# parts_servo.net
KiCad netlist of a schematic drawn in EAGLE
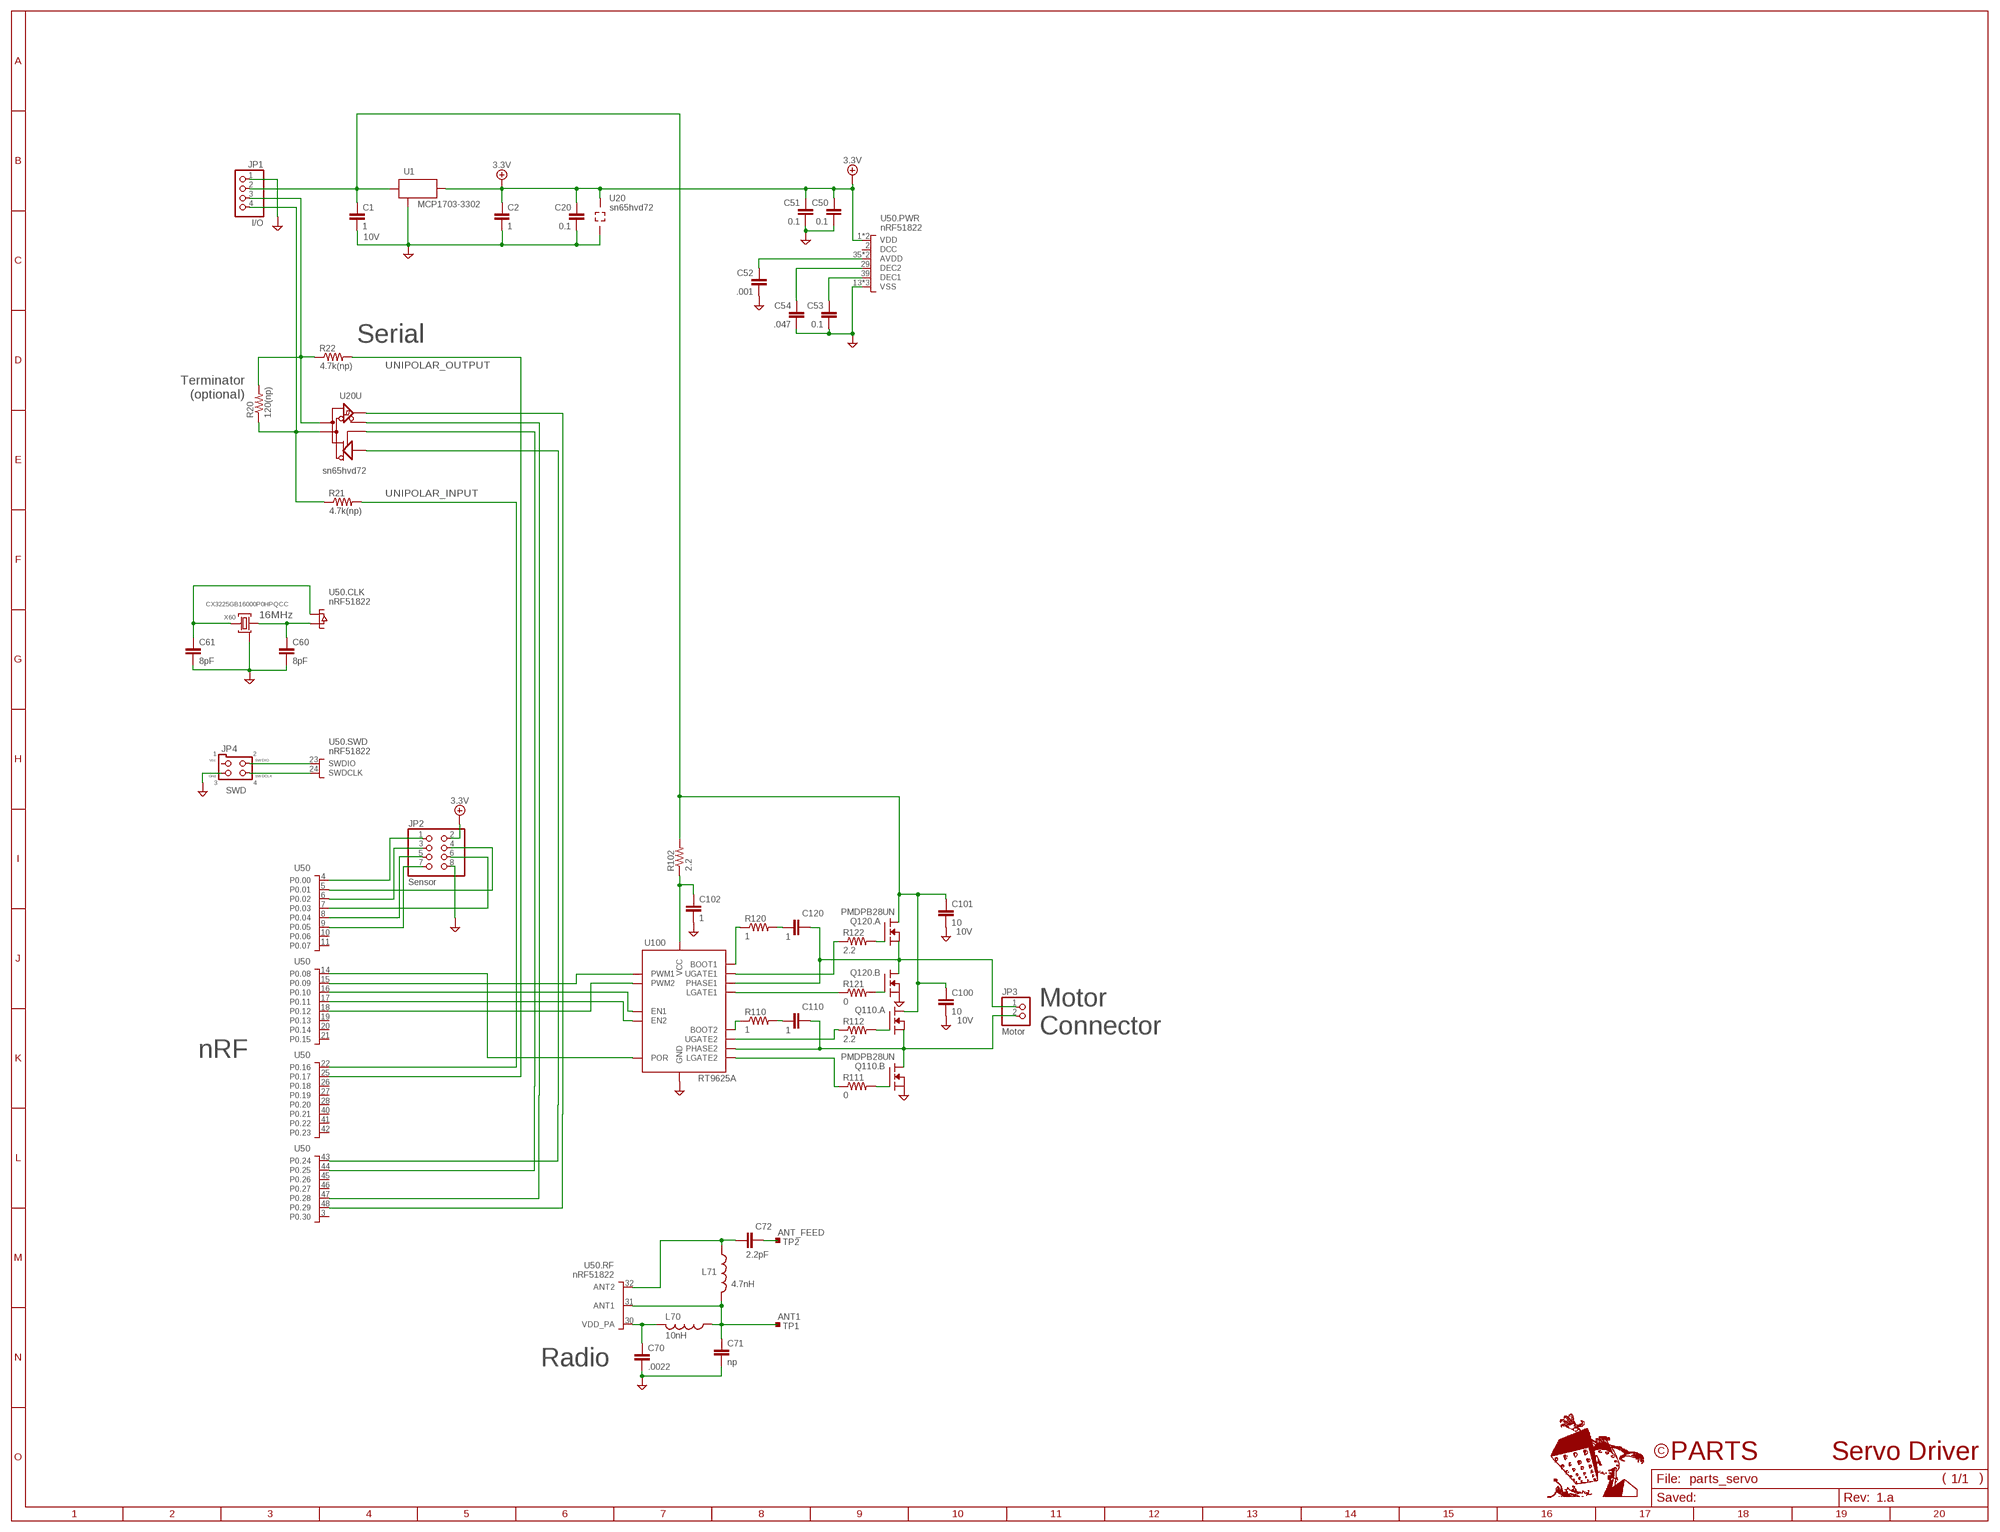
[diagram p0: schematic, sheet 1]

(export (version "E")
  (design (tool "Eeschema 10.0.6"))
  (components
    (comp (ref "C1")
      (value "1")
      (footprint "eagle-import:0402-B")
      (fields (field (name "VOLTAGE") "10V"))
      (libsource (lib "eagle-import") (part "C-EU0402-B"))
    )
    (comp (ref "C2")
      (value "1")
      (footprint "eagle-import:0402-B")
      (libsource (lib "eagle-import") (part "C-EU0402-B"))
    )
    (comp (ref "C20")
      (value "0.1")
      (footprint "eagle-import:0402-B")
      (libsource (lib "eagle-import") (part "C-EU0402-B"))
    )
    (comp (ref "C50")
      (value "0.1")
      (footprint "eagle-import:0402-B")
      (libsource (lib "eagle-import") (part "C-EU0402-B"))
    )
    (comp (ref "C51")
      (value "0.1")
      (footprint "eagle-import:0402-B")
      (libsource (lib "eagle-import") (part "C-EU0402-B"))
    )
    (comp (ref "C52")
      (value ".001")
      (footprint "eagle-import:0402-B")
      (libsource (lib "eagle-import") (part "C-EU0402-B"))
    )
    (comp (ref "C53")
      (value "0.1")
      (footprint "eagle-import:0402-B")
      (libsource (lib "eagle-import") (part "C-EU0402-B"))
    )
    (comp (ref "C54")
      (value ".047")
      (footprint "eagle-import:0402-B")
      (libsource (lib "eagle-import") (part "C-EU0402-B"))
    )
    (comp (ref "C60")
      (value "8pF")
      (footprint "eagle-import:0402-B")
      (libsource (lib "eagle-import") (part "C-EU0402-B"))
    )
    (comp (ref "C61")
      (value "8pF")
      (footprint "eagle-import:0402-B")
      (libsource (lib "eagle-import") (part "C-EU0402-B"))
    )
    (comp (ref "C70")
      (value ".0022")
      (footprint "eagle-import:0402-B")
      (libsource (lib "eagle-import") (part "C-EU0402-B"))
    )
    (comp (ref "C71")
      (value "np")
      (footprint "eagle-import:0402-B")
      (libsource (lib "eagle-import") (part "C-EU0402-B"))
    )
    (comp (ref "C72")
      (value "2.2pF")
      (footprint "eagle-import:0402-B")
      (libsource (lib "eagle-import") (part "C-EU0402-B"))
    )
    (comp (ref "C100")
      (value "10")
      (footprint "eagle-import:0805-B")
      (fields (field (name "VOLTAGE") "10V"))
      (libsource (lib "eagle-import") (part "C-EU0805-B"))
    )
    (comp (ref "C101")
      (value "10")
      (footprint "eagle-import:0805-B")
      (fields (field (name "VOLTAGE") "10V"))
      (libsource (lib "eagle-import") (part "C-EU0805-B"))
    )
    (comp (ref "C102")
      (value "1")
      (footprint "eagle-import:0402-B")
      (libsource (lib "eagle-import") (part "C-EU0402-B"))
    )
    (comp (ref "C110")
      (value "1")
      (footprint "eagle-import:0402-B")
      (libsource (lib "eagle-import") (part "C-EU0402-B"))
    )
    (comp (ref "C120")
      (value "1")
      (footprint "eagle-import:0402-B")
      (libsource (lib "eagle-import") (part "C-EU0402-B"))
    )
    (comp (ref "JP1")
      (value "I/O")
      (footprint "eagle-import:1X04")
      (libsource (lib "eagle-import") (part "PINHD-1X4"))
    )
    (comp (ref "JP2")
      (value "Sensor")
      (footprint "eagle-import:2X04")
      (libsource (lib "eagle-import") (part "PINHD-2X4"))
    )
    (comp (ref "JP3")
      (value "Motor")
      (footprint "eagle-import:1X02")
      (libsource (lib "eagle-import") (part "PINHD-1X2"))
    )
    (comp (ref "JP4")
      (value "SWD")
      (footprint "eagle-import:PINHEADER-2X2-0.05_IN")
      (libsource (lib "eagle-import") (part "SWD-ARM_MINI"))
    )
    (comp (ref "L70")
      (value "10nH")
      (footprint "eagle-import:0402-B")
      (libsource (lib "eagle-import") (part "L-US0402-B"))
    )
    (comp (ref "L71")
      (value "4.7nH")
      (footprint "eagle-import:0402-B")
      (libsource (lib "eagle-import") (part "L-US0402-B"))
    )
    (comp (ref "Q110")
      (value "PMDPB28UN")
      (footprint "eagle-import:DFN-6(2X2)+2EP(TRANSISTOR)")
      (libsource (lib "eagle-import") (part "NFET-DUAL-DFN-6(2X2)+2PADS"))
    )
    (comp (ref "Q120")
      (value "PMDPB28UN")
      (footprint "eagle-import:DFN-6(2X2)+2EP(TRANSISTOR)")
      (libsource (lib "eagle-import") (part "NFET-DUAL-DFN-6(2X2)+2PADS"))
    )
    (comp (ref "R20")
      (value "120(np)")
      (footprint "eagle-import:0402-B")
      (libsource (lib "eagle-import") (part "R-US_0402-B"))
    )
    (comp (ref "R21")
      (value "4.7k(np)")
      (footprint "eagle-import:0402-B")
      (libsource (lib "eagle-import") (part "R-US_0402-B"))
    )
    (comp (ref "R22")
      (value "4.7k(np)")
      (footprint "eagle-import:0402-B")
      (libsource (lib "eagle-import") (part "R-US_0402-B"))
    )
    (comp (ref "R102")
      (value "2.2")
      (footprint "eagle-import:0402-B")
      (libsource (lib "eagle-import") (part "R-US_0402-B"))
    )
    (comp (ref "R110")
      (value "1")
      (footprint "eagle-import:0402-B")
      (libsource (lib "eagle-import") (part "R-US_0402-B"))
    )
    (comp (ref "R111")
      (value "0")
      (footprint "eagle-import:0402-B")
      (libsource (lib "eagle-import") (part "R-US_0402-B"))
    )
    (comp (ref "R112")
      (value "2.2")
      (footprint "eagle-import:0402-B")
      (libsource (lib "eagle-import") (part "R-US_0402-B"))
    )
    (comp (ref "R120")
      (value "1")
      (footprint "eagle-import:0402-B")
      (libsource (lib "eagle-import") (part "R-US_0402-B"))
    )
    (comp (ref "R121")
      (value "0")
      (footprint "eagle-import:0402-B")
      (libsource (lib "eagle-import") (part "R-US_0402-B"))
    )
    (comp (ref "R122")
      (value "2.2")
      (footprint "eagle-import:0402-B")
      (libsource (lib "eagle-import") (part "R-US_0402-B"))
    )
    (comp (ref "TP1")
      (value "ANT1")
      (footprint "eagle-import:TESTPOINT-(1X1)CREAMED")
      (libsource (lib "eagle-import") (part "TESTPAD-(1X1)CREAMED"))
    )
    (comp (ref "TP2")
      (value "ANT_FEED")
      (footprint "eagle-import:TESTPOINT-(1X1)CREAMED")
      (libsource (lib "eagle-import") (part "TESTPAD-(1X1)CREAMED"))
    )
    (comp (ref "U1")
      (value "MCP1703-3302")
      (footprint "eagle-import:DFN-8(2X3)+EP")
      (libsource (lib "eagle-import") (part "VOLTAGE_REGULATOR-3_TERMINAL"))
    )
    (comp (ref "U20")
      (value "sn65hvd72")
      (footprint "eagle-import:DFN-8(3X3)+EP")
      (libsource (lib "eagle-import") (part "DIFFERENTIAL_TRANSCEIVER-DFN-8(3X3)+EP"))
    )
    (comp (ref "U50")
      (value "nRF51822")
      (footprint "eagle-import:DFN-48(6X6)+EP")
      (fields (field (name "SWDIO") "(nRST)"))
      (libsource (lib "eagle-import") (part "NRF51822-QFN-48(6X6)"))
    )
    (comp (ref "U100")
      (value "RT9625A")
      (footprint "eagle-import:QFN-16(4X4)+EP")
      (libsource (lib "eagle-import") (part "HALF_BRIDGE_DRIVER-DUAL-QFN-16(4X4)"))
    )
    (comp (ref "X60")
      (value "CX3225GB16000P0HPQCC")
      (footprint "eagle-import:CRYSTAL-3.2X2.5(4_TERMINAL)")
      (fields (field (name "FREQUENCY") "16MHz"))
      (libsource (lib "eagle-import") (part "CRYSTAL_SHIELDED-3.2X2.5"))
    )
  )
  (nets
    (net (code "1") (name "/UNIPOLAR_INPUT") (class "Default")
      (node (ref "R21") (pin "2") (pinfunction "2_2") (pintype "passive"))
      (node (ref "U50") (pin "22") (pinfunction "P0.16_22") (pintype "bidirectional"))
    )
    (net (code "2") (name "/UNIPOLAR_OUTPUT") (class "Default")
      (node (ref "R22") (pin "2") (pinfunction "2_2") (pintype "passive"))
      (node (ref "U50") (pin "25") (pinfunction "P0.17_25") (pintype "bidirectional"))
    )
    (net (code "3") (name "3.3V") (class "Default")
      (node (ref "C2") (pin "1") (pinfunction "1_1") (pintype "passive"))
      (node (ref "C20") (pin "1") (pinfunction "1_1") (pintype "passive"))
      (node (ref "C50") (pin "1") (pinfunction "1_1") (pintype "passive"))
      (node (ref "C51") (pin "1") (pinfunction "1_1") (pintype "passive"))
      (node (ref "JP2") (pin "2") (pinfunction "2_2") (pintype "passive"))
      (node (ref "U1") (pin "1") (pinfunction "OUT_1") (pintype "power_in"))
      (node (ref "U20") (pin "8") (pinfunction "VDD_8") (pintype "power_in"))
      (node (ref "U50") (pin "1") (pinfunction "VDD_1") (pintype "power_in"))
      (node (ref "U50") (pin "12") (pinfunction "VDD_12") (pintype "power_in"))
    )
    (net (code "4") (name "GND_TRIANGLE-GND") (class "Default")
      (node (ref "C1") (pin "2") (pinfunction "2_2") (pintype "passive"))
      (node (ref "C100") (pin "2") (pinfunction "2_2") (pintype "passive"))
      (node (ref "C101") (pin "2") (pinfunction "2_2") (pintype "passive"))
      (node (ref "C102") (pin "2") (pinfunction "2_2") (pintype "passive"))
      (node (ref "C2") (pin "2") (pinfunction "2_2") (pintype "passive"))
      (node (ref "C20") (pin "2") (pinfunction "2_2") (pintype "passive"))
      (node (ref "C50") (pin "2") (pinfunction "2_2") (pintype "passive"))
      (node (ref "C51") (pin "2") (pinfunction "2_2") (pintype "passive"))
      (node (ref "C52") (pin "2") (pinfunction "2_2") (pintype "passive"))
      (node (ref "C53") (pin "2") (pinfunction "2_2") (pintype "passive"))
      (node (ref "C54") (pin "2") (pinfunction "2_2") (pintype "passive"))
      (node (ref "C60") (pin "2") (pinfunction "2_2") (pintype "passive"))
      (node (ref "C61") (pin "2") (pinfunction "2_2") (pintype "passive"))
      (node (ref "C70") (pin "2") (pinfunction "2_2") (pintype "passive"))
      (node (ref "C71") (pin "2") (pinfunction "2_2") (pintype "passive"))
      (node (ref "JP1") (pin "1") (pinfunction "1_1") (pintype "passive"))
      (node (ref "JP2") (pin "8") (pinfunction "8_8") (pintype "passive"))
      (node (ref "JP4") (pin "3") (pinfunction "GND_3") (pintype "passive"))
      (node (ref "Q110") (pin "4") (pinfunction "S_4") (pintype "passive"))
      (node (ref "Q120") (pin "4") (pinfunction "S_4") (pintype "passive"))
      (node (ref "U1") (pin "4") (pinfunction "GND_4") (pintype "power_in"))
      (node (ref "U1") (pin "PAD") (pinfunction "GND_PAD") (pintype "power_in"))
      (node (ref "U100") (pin "13") (pinfunction "GND_13") (pintype "power_in"))
      (node (ref "U100") (pin "2") (pinfunction "GND_2") (pintype "power_in"))
      (node (ref "U100") (pin "PAD") (pinfunction "GND_PAD") (pintype "power_in"))
      (node (ref "U20") (pin "5") (pinfunction "GND_5") (pintype "power_in"))
      (node (ref "U20") (pin "PAD") (pinfunction "GND_PAD") (pintype "power_in"))
      (node (ref "U50") (pin "13") (pinfunction "VSS_13") (pintype "power_in"))
      (node (ref "U50") (pin "33") (pinfunction "VSS_33") (pintype "power_in"))
      (node (ref "U50") (pin "34") (pinfunction "VSS_34") (pintype "power_in"))
      (node (ref "X60") (pin "2") (pinfunction "SHIELD_2") (pintype "passive"))
      (node (ref "X60") (pin "4") (pinfunction "SHIELD_4") (pintype "passive"))
    )
    (net (code "5") (name "Net-(C52-Pad1)") (class "Default")
      (node (ref "C52") (pin "1") (pinfunction "1_1") (pintype "passive"))
      (node (ref "U50") (pin "35") (pinfunction "AVDD_35") (pintype "power_in"))
      (node (ref "U50") (pin "36") (pinfunction "AVDD_36") (pintype "power_in"))
    )
    (net (code "6") (name "Net-(C72-Pad2)") (class "Default")
      (node (ref "C72") (pin "2") (pinfunction "2_2") (pintype "passive"))
      (node (ref "TP2") (pin "TP") (pinfunction "TP_TP") (pintype "passive"))
    )
    (net (code "7") (name "Net-(C110-Pad1)") (class "Default")
      (node (ref "C110") (pin "1") (pinfunction "1_1") (pintype "passive"))
      (node (ref "R110") (pin "2") (pinfunction "2_2") (pintype "passive"))
    )
    (net (code "8") (name "Net-(C120-Pad1)") (class "Default")
      (node (ref "C120") (pin "1") (pinfunction "1_1") (pintype "passive"))
      (node (ref "R120") (pin "2") (pinfunction "2_2") (pintype "passive"))
    )
    (net (code "9") (name "Net-(JP4-SWDCLK)") (class "Default")
      (node (ref "JP4") (pin "4") (pinfunction "SWDCLK_4") (pintype "passive"))
      (node (ref "U50") (pin "24") (pinfunction "SWDCLK_24") (pintype "input"))
    )
    (net (code "10") (name "Net-(JP4-SWDIO)") (class "Default")
      (node (ref "JP4") (pin "2") (pinfunction "SWDIO_2") (pintype "passive"))
      (node (ref "U50") (pin "23") (pinfunction "SWDIO_23") (pintype "bidirectional"))
    )
    (net (code "11") (name "Net-(Q110A-G)") (class "Default")
      (node (ref "Q110") (pin "2") (pinfunction "G_2") (pintype "passive"))
      (node (ref "R112") (pin "2") (pinfunction "2_2") (pintype "passive"))
    )
    (net (code "12") (name "Net-(Q110A-S)") (class "Default")
      (node (ref "C110") (pin "2") (pinfunction "2_2") (pintype "passive"))
      (node (ref "JP3") (pin "2") (pinfunction "2_2") (pintype "passive"))
      (node (ref "Q110") (pin "1") (pinfunction "S_1") (pintype "passive"))
      (node (ref "Q110") (pin "3") (pinfunction "D_3") (pintype "passive"))
      (node (ref "Q110") (pin "P8") (pinfunction "D_P8") (pintype "passive"))
      (node (ref "U100") (pin "15") (pinfunction "PHASE2_15") (pintype "input"))
    )
    (net (code "13") (name "Net-(Q110B-G)") (class "Default")
      (node (ref "Q110") (pin "5") (pinfunction "G_5") (pintype "passive"))
      (node (ref "R111") (pin "2") (pinfunction "2_2") (pintype "passive"))
    )
    (net (code "14") (name "Net-(Q120A-G)") (class "Default")
      (node (ref "Q120") (pin "2") (pinfunction "G_2") (pintype "passive"))
      (node (ref "R122") (pin "2") (pinfunction "2_2") (pintype "passive"))
    )
    (net (code "15") (name "Net-(Q120A-S)") (class "Default")
      (node (ref "C120") (pin "2") (pinfunction "2_2") (pintype "passive"))
      (node (ref "JP3") (pin "1") (pinfunction "1_1") (pintype "passive"))
      (node (ref "Q120") (pin "1") (pinfunction "S_1") (pintype "passive"))
      (node (ref "Q120") (pin "3") (pinfunction "D_3") (pintype "passive"))
      (node (ref "Q120") (pin "P8") (pinfunction "D_P8") (pintype "passive"))
      (node (ref "U100") (pin "10") (pinfunction "PHASE1_10") (pintype "input"))
    )
    (net (code "16") (name "Net-(Q120B-G)") (class "Default")
      (node (ref "Q120") (pin "5") (pinfunction "G_5") (pintype "passive"))
      (node (ref "R121") (pin "2") (pinfunction "2_2") (pintype "passive"))
    )
    (net (code "17") (name "Net-(U1-IN)") (class "Default")
      (node (ref "C1") (pin "1") (pinfunction "1_1") (pintype "passive"))
      (node (ref "C100") (pin "1") (pinfunction "1_1") (pintype "passive"))
      (node (ref "C101") (pin "1") (pinfunction "1_1") (pintype "passive"))
      (node (ref "JP1") (pin "2") (pinfunction "2_2") (pintype "passive"))
      (node (ref "Q110") (pin "6") (pinfunction "D_6") (pintype "passive"))
      (node (ref "Q110") (pin "P7") (pinfunction "D_P7") (pintype "passive"))
      (node (ref "Q120") (pin "6") (pinfunction "D_6") (pintype "passive"))
      (node (ref "Q120") (pin "P7") (pinfunction "D_P7") (pintype "passive"))
      (node (ref "R102") (pin "2") (pinfunction "2_2") (pintype "passive"))
      (node (ref "U1") (pin "8") (pinfunction "IN_8") (pintype "power_in"))
    )
    (net (code "18") (name "Net-(U20B-A)") (class "Default")
      (node (ref "JP1") (pin "3") (pinfunction "3_3") (pintype "passive"))
      (node (ref "R20") (pin "2") (pinfunction "2_2") (pintype "passive"))
      (node (ref "R22") (pin "1") (pinfunction "1_1") (pintype "passive"))
      (node (ref "U20") (pin "6") (pinfunction "A_6") (pintype "bidirectional"))
    )
    (net (code "19") (name "Net-(U20B-B)") (class "Default")
      (node (ref "JP1") (pin "4") (pinfunction "4_4") (pintype "passive"))
      (node (ref "R20") (pin "1") (pinfunction "1_1") (pintype "passive"))
      (node (ref "R21") (pin "1") (pinfunction "1_1") (pintype "passive"))
      (node (ref "U20") (pin "7") (pinfunction "B_7") (pintype "bidirectional"))
    )
    (net (code "20") (name "Net-(U20B-D)") (class "Default")
      (node (ref "U20") (pin "4") (pinfunction "D_4") (pintype "input"))
      (node (ref "U50") (pin "43") (pinfunction "P0.24_43") (pintype "bidirectional"))
    )
    (net (code "21") (name "Net-(U20B-DE)") (class "Default")
      (node (ref "U20") (pin "3") (pinfunction "DE_3") (pintype "input"))
      (node (ref "U50") (pin "44") (pinfunction "P0.25_44") (pintype "bidirectional"))
    )
    (net (code "22") (name "Net-(U20B-R)") (class "Default")
      (node (ref "U20") (pin "1") (pinfunction "R_1") (pintype "output"))
      (node (ref "U50") (pin "48") (pinfunction "P0.29_48") (pintype "bidirectional"))
    )
    (net (code "23") (name "Net-(U20B-~{RE})") (class "Default")
      (node (ref "U20") (pin "2") (pinfunction "~{RE}_2") (pintype "input"))
      (node (ref "U50") (pin "47") (pinfunction "P0.28_47") (pintype "bidirectional"))
    )
    (net (code "24") (name "Net-(U50A-CLKIN)") (class "Default")
      (node (ref "C60") (pin "1") (pinfunction "1_1") (pintype "passive"))
      (node (ref "U50") (pin "37") (pinfunction "CLKIN_37") (pintype "input"))
      (node (ref "X60") (pin "1") (pinfunction "1_1") (pintype "passive"))
    )
    (net (code "25") (name "Net-(U50A-CLKOUT)") (class "Default")
      (node (ref "C61") (pin "1") (pinfunction "1_1") (pintype "passive"))
      (node (ref "U50") (pin "38") (pinfunction "CLKOUT_38") (pintype "output"))
      (node (ref "X60") (pin "3") (pinfunction "2_3") (pintype "passive"))
    )
    (net (code "26") (name "Net-(U50B-DEC1)") (class "Default")
      (node (ref "C53") (pin "1") (pinfunction "1_1") (pintype "passive"))
      (node (ref "U50") (pin "39") (pinfunction "DEC1_39") (pintype "passive"))
    )
    (net (code "27") (name "Net-(U50B-DEC2)") (class "Default")
      (node (ref "C54") (pin "1") (pinfunction "1_1") (pintype "passive"))
      (node (ref "U50") (pin "29") (pinfunction "DEC2_29") (pintype "passive"))
    )
    (net (code "28") (name "Net-(U50C-ANT1)") (class "Default")
      (node (ref "C71") (pin "1") (pinfunction "1_1") (pintype "passive"))
      (node (ref "L70") (pin "1") (pinfunction "1_1") (pintype "passive"))
      (node (ref "L71") (pin "2") (pinfunction "2_2") (pintype "passive"))
      (node (ref "TP1") (pin "TP") (pinfunction "TP_TP") (pintype "passive"))
      (node (ref "U50") (pin "31") (pinfunction "ANT1_31") (pintype "passive"))
    )
    (net (code "29") (name "Net-(U50C-ANT2)") (class "Default")
      (node (ref "C72") (pin "1") (pinfunction "1_1") (pintype "passive"))
      (node (ref "L71") (pin "1") (pinfunction "1_1") (pintype "passive"))
      (node (ref "U50") (pin "32") (pinfunction "ANT2_32") (pintype "passive"))
    )
    (net (code "30") (name "Net-(U50C-VDD_PA)") (class "Default")
      (node (ref "C70") (pin "1") (pinfunction "1_1") (pintype "passive"))
      (node (ref "L70") (pin "2") (pinfunction "2_2") (pintype "passive"))
      (node (ref "U50") (pin "30") (pinfunction "VDD_PA_30") (pintype "passive"))
    )
    (net (code "31") (name "Net-(U50E-P0.00)") (class "Default")
      (node (ref "JP2") (pin "1") (pinfunction "1_1") (pintype "passive"))
      (node (ref "U50") (pin "4") (pinfunction "P0.00_4") (pintype "bidirectional"))
    )
    (net (code "32") (name "Net-(U50E-P0.01)") (class "Default")
      (node (ref "JP2") (pin "4") (pinfunction "4_4") (pintype "passive"))
      (node (ref "U50") (pin "5") (pinfunction "P0.01_5") (pintype "bidirectional"))
    )
    (net (code "33") (name "Net-(U50E-P0.02)") (class "Default")
      (node (ref "JP2") (pin "3") (pinfunction "3_3") (pintype "passive"))
      (node (ref "U50") (pin "6") (pinfunction "P0.02_6") (pintype "bidirectional"))
    )
    (net (code "34") (name "Net-(U50E-P0.03)") (class "Default")
      (node (ref "JP2") (pin "6") (pinfunction "6_6") (pintype "passive"))
      (node (ref "U50") (pin "7") (pinfunction "P0.03_7") (pintype "bidirectional"))
    )
    (net (code "35") (name "Net-(U50E-P0.04)") (class "Default")
      (node (ref "JP2") (pin "5") (pinfunction "5_5") (pintype "passive"))
      (node (ref "U50") (pin "8") (pinfunction "P0.04_8") (pintype "bidirectional"))
    )
    (net (code "36") (name "Net-(U50E-P0.05)") (class "Default")
      (node (ref "JP2") (pin "7") (pinfunction "7_7") (pintype "passive"))
      (node (ref "U50") (pin "9") (pinfunction "P0.05_9") (pintype "bidirectional"))
    )
    (net (code "37") (name "Net-(U100-BOOT1)") (class "Default")
      (node (ref "R120") (pin "1") (pinfunction "1_1") (pintype "passive"))
      (node (ref "U100") (pin "8") (pinfunction "BOOT1_8") (pintype "passive"))
    )
    (net (code "38") (name "Net-(U100-BOOT2)") (class "Default")
      (node (ref "R110") (pin "1") (pinfunction "1_1") (pintype "passive"))
      (node (ref "U100") (pin "1") (pinfunction "BOOT2_1") (pintype "output"))
    )
    (net (code "39") (name "Net-(U100-EN1)") (class "Default")
      (node (ref "U100") (pin "5") (pinfunction "EN1_5") (pintype "input"))
      (node (ref "U50") (pin "16") (pinfunction "P0.10_16") (pintype "bidirectional"))
    )
    (net (code "40") (name "Net-(U100-EN2)") (class "Default")
      (node (ref "U100") (pin "4") (pinfunction "EN2_4") (pintype "input"))
      (node (ref "U50") (pin "17") (pinfunction "P0.11_17") (pintype "bidirectional"))
    )
    (net (code "41") (name "Net-(U100-LGATE1)") (class "Default")
      (node (ref "R121") (pin "1") (pinfunction "1_1") (pintype "passive"))
      (node (ref "U100") (pin "11") (pinfunction "LGATE1_11") (pintype "output"))
    )
    (net (code "42") (name "Net-(U100-LGATE2)") (class "Default")
      (node (ref "R111") (pin "1") (pinfunction "1_1") (pintype "passive"))
      (node (ref "U100") (pin "14") (pinfunction "LGATE2_14") (pintype "passive"))
    )
    (net (code "43") (name "Net-(U100-POR)") (class "Default")
      (node (ref "U100") (pin "7") (pinfunction "POR_7") (pintype "bidirectional"))
      (node (ref "U50") (pin "14") (pinfunction "P0.08_14") (pintype "bidirectional"))
    )
    (net (code "44") (name "Net-(U100-PWM1)") (class "Default")
      (node (ref "U100") (pin "6") (pinfunction "PWM1_6") (pintype "input"))
      (node (ref "U50") (pin "15") (pinfunction "P0.09_15") (pintype "bidirectional"))
    )
    (net (code "45") (name "Net-(U100-PWM2)") (class "Default")
      (node (ref "U100") (pin "3") (pinfunction "PWM2_3") (pintype "input"))
      (node (ref "U50") (pin "18") (pinfunction "P0.12_18") (pintype "bidirectional"))
    )
    (net (code "46") (name "Net-(U100-UGATE1)") (class "Default")
      (node (ref "R122") (pin "1") (pinfunction "1_1") (pintype "passive"))
      (node (ref "U100") (pin "9") (pinfunction "UGATE1_9") (pintype "output"))
    )
    (net (code "47") (name "Net-(U100-UGATE2)") (class "Default")
      (node (ref "R112") (pin "1") (pinfunction "1_1") (pintype "passive"))
      (node (ref "U100") (pin "16") (pinfunction "UGATE2_16") (pintype "output"))
    )
    (net (code "48") (name "Net-(U100-VCC)") (class "Default")
      (node (ref "C102") (pin "1") (pinfunction "1_1") (pintype "passive"))
      (node (ref "R102") (pin "1") (pinfunction "1_1") (pintype "passive"))
      (node (ref "U100") (pin "12") (pinfunction "VCC_12") (pintype "power_in"))
    )
    (net (code "49") (name "unconnected-(JP4-VCC-Pad1)") (class "Default")
      (node (ref "JP4") (pin "1") (pinfunction "VCC_1") (pintype "passive"))
    )
    (net (code "50") (name "unconnected-(U50B-DCC-Pad2)") (class "Default")
      (node (ref "U50") (pin "2") (pinfunction "DCC_2") (pintype "passive"))
    )
    (net (code "51") (name "unconnected-(U50E-P0.06-Pad10)") (class "Default")
      (node (ref "U50") (pin "10") (pinfunction "P0.06_10") (pintype "bidirectional"))
    )
    (net (code "52") (name "unconnected-(U50E-P0.07-Pad11)") (class "Default")
      (node (ref "U50") (pin "11") (pinfunction "P0.07_11") (pintype "bidirectional"))
    )
    (net (code "53") (name "unconnected-(U50F-P0.13-Pad19)") (class "Default")
      (node (ref "U50") (pin "19") (pinfunction "P0.13_19") (pintype "bidirectional"))
    )
    (net (code "54") (name "unconnected-(U50F-P0.14-Pad20)") (class "Default")
      (node (ref "U50") (pin "20") (pinfunction "P0.14_20") (pintype "bidirectional"))
    )
    (net (code "55") (name "unconnected-(U50F-P0.15-Pad21)") (class "Default")
      (node (ref "U50") (pin "21") (pinfunction "P0.15_21") (pintype "bidirectional"))
    )
    (net (code "56") (name "unconnected-(U50G-P0.18-Pad26)") (class "Default")
      (node (ref "U50") (pin "26") (pinfunction "P0.18_26") (pintype "bidirectional"))
    )
    (net (code "57") (name "unconnected-(U50G-P0.19-Pad27)") (class "Default")
      (node (ref "U50") (pin "27") (pinfunction "P0.19_27") (pintype "bidirectional"))
    )
    (net (code "58") (name "unconnected-(U50G-P0.20-Pad28)") (class "Default")
      (node (ref "U50") (pin "28") (pinfunction "P0.20_28") (pintype "bidirectional"))
    )
    (net (code "59") (name "unconnected-(U50G-P0.21-Pad40)") (class "Default")
      (node (ref "U50") (pin "40") (pinfunction "P0.21_40") (pintype "bidirectional"))
    )
    (net (code "60") (name "unconnected-(U50G-P0.22-Pad41)") (class "Default")
      (node (ref "U50") (pin "41") (pinfunction "P0.22_41") (pintype "bidirectional"))
    )
    (net (code "61") (name "unconnected-(U50G-P0.23-Pad42)") (class "Default")
      (node (ref "U50") (pin "42") (pinfunction "P0.23_42") (pintype "bidirectional"))
    )
    (net (code "62") (name "unconnected-(U50H-P0.26-Pad45)") (class "Default")
      (node (ref "U50") (pin "45") (pinfunction "P0.26_45") (pintype "bidirectional"))
    )
    (net (code "63") (name "unconnected-(U50H-P0.27-Pad46)") (class "Default")
      (node (ref "U50") (pin "46") (pinfunction "P0.27_46") (pintype "bidirectional"))
    )
    (net (code "64") (name "unconnected-(U50H-P0.30-Pad3)") (class "Default")
      (node (ref "U50") (pin "3") (pinfunction "P0.30_3") (pintype "bidirectional"))
    )
  )
)
